# 51_ADC.net
KiCad netlist of a schematic drawn in Altium Designer
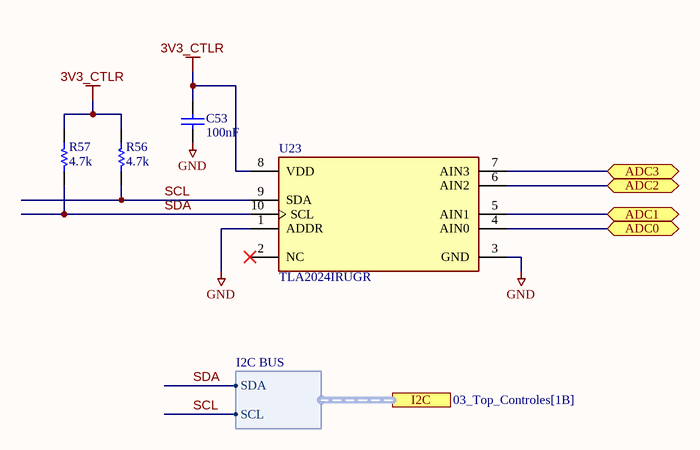
[diagram p0: 51_ADC.SchDoc]

(export (version "E")
  (design (tool "Eeschema 10.0.6"))
  (components
    (comp (ref "C53")
      (value "100nF")
      (footprint "CAPC1005X55X25NL05T05")
      (fields (field (name "MANUFACTURER") "Vitramon") (field (name "PART NUMBER") "VJ0402Y104KXJCW1BC"))
      (libsource (lib "Altium Content Vault") (part "CAP"))
    )
    (comp (ref "R56")
      (value "4.7k")
      (footprint "RESC1005X40X25ML05T10")
      (fields (field (name "MANUFACTURER") "Panasonic") (field (name "PART NUMBER") "ERJ-S02F4701X"))
      (libsource (lib "Altium Content Vault") (part "RES"))
    )
    (comp (ref "R57")
      (value "4.7k")
      (footprint "RESC1005X40X25ML05T10")
      (fields (field (name "MANUFACTURER") "Panasonic") (field (name "PART NUMBER") "ERJ-S02F4701X"))
      (libsource (lib "Altium Content Vault") (part "RES"))
    )
    (comp (ref "U23")
      (value "TLA2024IRUGR")
      (footprint "FP-RUG0010A-MFG")
      (description "IC ADC 12BIT SIGMA-DELTA 10X2QFN")
      (libsource (lib "Altium Content Vault") (part "eb3f1feaf096e0a4fed058628c4118d"))
    )
  )
  (nets
    (net (code "3") (name "/ADC0") (class "Default")
      (node (ref "U23") (pin "4") (pinfunction "AIN0_4") (pintype "passive"))
    )
    (net (code "4") (name "/ADC1") (class "Default")
      (node (ref "U23") (pin "5") (pinfunction "AIN1_5") (pintype "passive"))
    )
    (net (code "5") (name "/ADC2") (class "Default")
      (node (ref "U23") (pin "6") (pinfunction "AIN2_6") (pintype "passive"))
    )
    (net (code "6") (name "/ADC3") (class "Default")
      (node (ref "U23") (pin "7") (pinfunction "AIN3_7") (pintype "passive"))
    )
    (net (code "7") (name "/SCL") (class "Default")
      (node (ref "R56") (pin "1") (pinfunction "1_1") (pintype "passive"))
      (node (ref "U23") (pin "9") (pinfunction "SDA_9") (pintype "passive"))
    )
    (net (code "8") (name "/SDA") (class "Default")
      (node (ref "R57") (pin "1") (pinfunction "1_1") (pintype "passive"))
      (node (ref "U23") (pin "10") (pinfunction "SCL_10") (pintype "passive"))
    )
    (net (code "10") (name "3V3_CTLR") (class "Default")
      (node (ref "C53") (pin "2") (pinfunction "2_2") (pintype "passive"))
      (node (ref "R56") (pin "2") (pinfunction "2_2") (pintype "passive"))
      (node (ref "R57") (pin "2") (pinfunction "2_2") (pintype "passive"))
      (node (ref "U23") (pin "8") (pinfunction "VDD_8") (pintype "passive"))
    )
    (net (code "11") (name "GND") (class "Default")
      (node (ref "C53") (pin "1") (pinfunction "1_1") (pintype "passive"))
      (node (ref "U23") (pin "1") (pinfunction "ADDR_1") (pintype "passive"))
      (node (ref "U23") (pin "3") (pinfunction "GND_3") (pintype "passive"))
    )
    (net (code "12") (name "unconnected-(U23-NC-Pad2)") (class "Default")
      (node (ref "U23") (pin "2") (pinfunction "NC_2") (pintype "passive+no_connect"))
    )
  )
)
